# ADC.net
KiCad netlist of a schematic drawn in Altium Designer
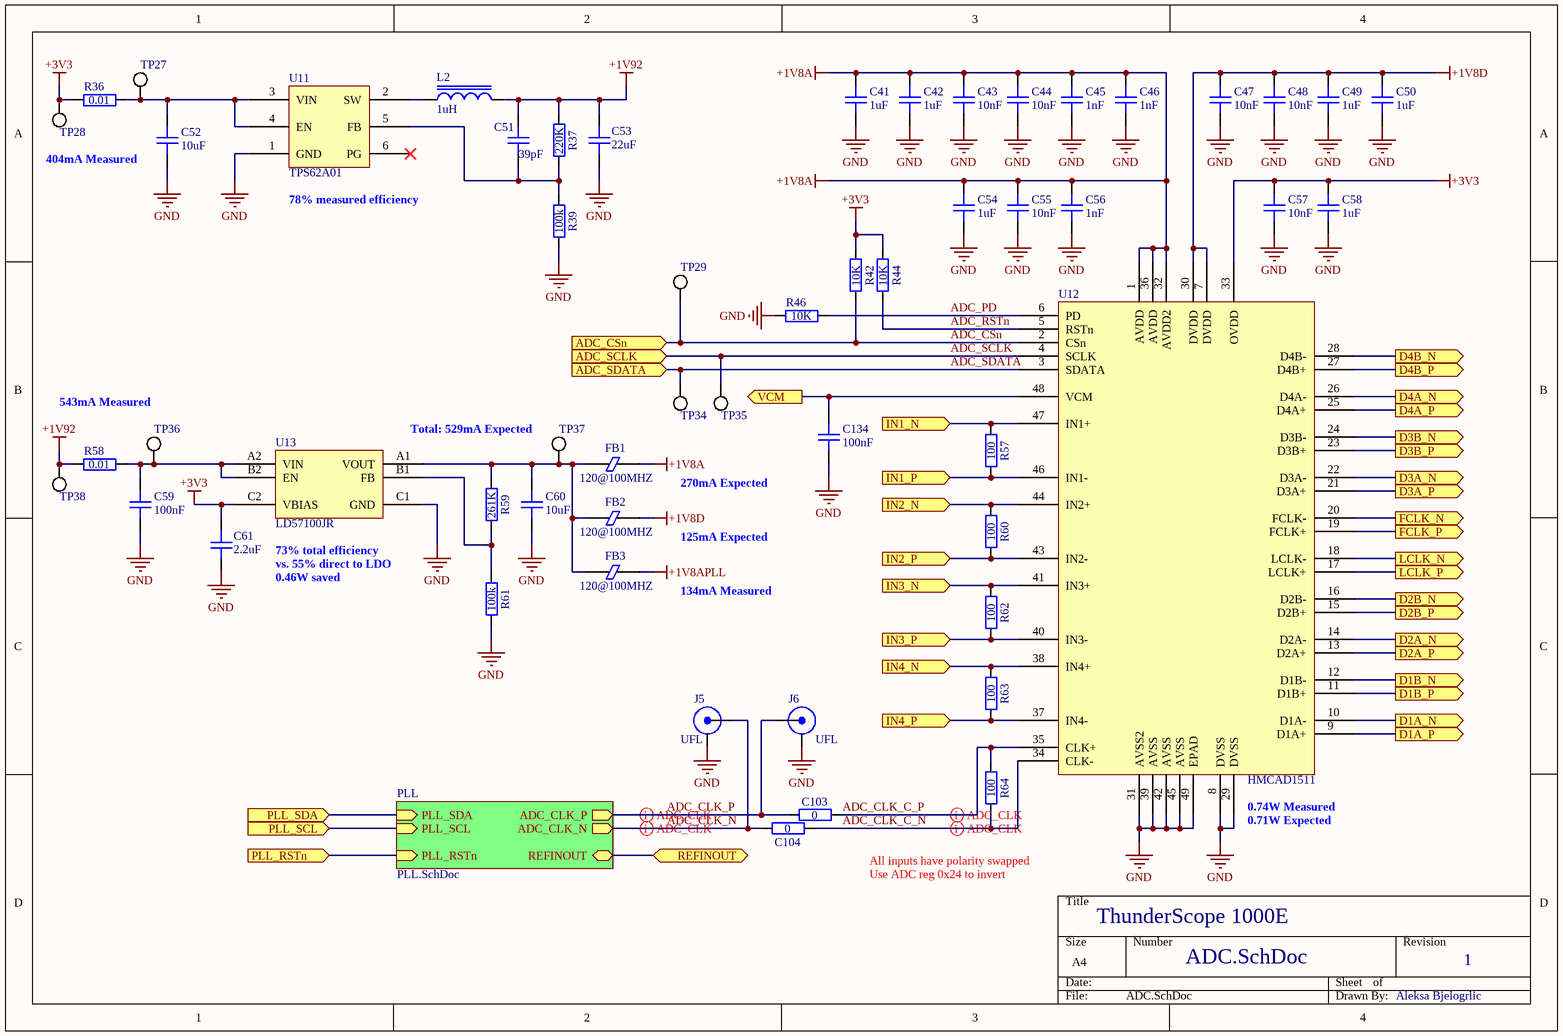
[diagram p0: ADC.SchDoc]

(export (version "E")
  (design (tool "Eeschema 10.0.6"))
  (components
    (comp (ref "C41")
      (value "1uF")
      (footprint "GEN_C_0402")
      (libsource (lib "DSO") (part "CAP 1uF 25V X5R 0402"))
    )
    (comp (ref "C42")
      (value "1uF")
      (footprint "GEN_C_0402")
      (libsource (lib "DSO") (part "CAP 1uF 25V X5R 0402"))
    )
    (comp (ref "C43")
      (value "10nF")
      (footprint "GEN_C_0402")
      (libsource (lib "DSO") (part "CAP 10nF 50V X7R 0402"))
    )
    (comp (ref "C44")
      (value "10nF")
      (footprint "GEN_C_0402")
      (libsource (lib "DSO") (part "CAP 10nF 50V X7R 0402"))
    )
    (comp (ref "C45")
      (value "1nF")
      (footprint "GEN_C_0402")
      (libsource (lib "DSO") (part "CAP 1nF 50V C0G 0402"))
    )
    (comp (ref "C46")
      (value "1nF")
      (footprint "GEN_C_0402")
      (libsource (lib "DSO") (part "CAP 1nF 50V C0G 0402"))
    )
    (comp (ref "C47")
      (value "10nF")
      (footprint "GEN_C_0402")
      (libsource (lib "DSO") (part "CAP 10nF 50V X7R 0402"))
    )
    (comp (ref "C48")
      (value "10nF")
      (footprint "GEN_C_0402")
      (libsource (lib "DSO") (part "CAP 10nF 50V X7R 0402"))
    )
    (comp (ref "C49")
      (value "1uF")
      (footprint "GEN_C_0402")
      (libsource (lib "DSO") (part "CAP 1uF 25V X5R 0402"))
    )
    (comp (ref "C50")
      (value "1uF")
      (footprint "GEN_C_0402")
      (libsource (lib "DSO") (part "CAP 1uF 25V X5R 0402"))
    )
    (comp (ref "C51")
      (value "39pF")
      (footprint "GEN_C_0402")
      (libsource (lib "DSO") (part "CAP 39pF 50V C0G 0402"))
    )
    (comp (ref "C52")
      (value "10uF")
      (footprint "GEN_C_0603")
      (libsource (lib "DSO") (part "CAP 10uF 10V X5R 0603"))
    )
    (comp (ref "C53")
      (value "22uF")
      (footprint "GEN_C_0805")
      (libsource (lib "DSO") (part "CAP 22uF 25V X5R 0805"))
    )
    (comp (ref "C54")
      (value "1uF")
      (footprint "GEN_C_0402")
      (libsource (lib "DSO") (part "CAP 1uF 25V X5R 0402"))
    )
    (comp (ref "C55")
      (value "10nF")
      (footprint "GEN_C_0402")
      (libsource (lib "DSO") (part "CAP 10nF 50V X7R 0402"))
    )
    (comp (ref "C56")
      (value "1nF")
      (footprint "GEN_C_0402")
      (libsource (lib "DSO") (part "CAP 1nF 50V C0G 0402"))
    )
    (comp (ref "C57")
      (value "10nF")
      (footprint "GEN_C_0402")
      (libsource (lib "DSO") (part "CAP 10nF 50V X7R 0402"))
    )
    (comp (ref "C58")
      (value "1uF")
      (footprint "GEN_C_0402")
      (libsource (lib "DSO") (part "CAP 1uF 25V X5R 0402"))
    )
    (comp (ref "C59")
      (value "100nF")
      (footprint "GEN_C_0402")
      (libsource (lib "DSO") (part "CAP 100nF 16V X7R 0402"))
    )
    (comp (ref "C60")
      (value "10uF")
      (footprint "GEN_C_0603")
      (libsource (lib "DSO") (part "CAP 10uF 10V X5R 0603"))
    )
    (comp (ref "C61")
      (value "2.2uF")
      (footprint "GEN_C_0402")
      (libsource (lib "DSO") (part "CAP 2.2uF 10V X5R 0402"))
    )
    (comp (ref "C103")
      (value "0")
      (footprint "GEN_R_0402")
      (fields
        (field (name "MANUFACTURER") "Yageo")
        (field (name "MANUFACTURER PART NUMBER") "RC0402JR-070RL")
      )
      (libsource (lib "DSO") (part "RES 0 OHM 1/16W 0402"))
    )
    (comp (ref "C104")
      (value "0")
      (footprint "GEN_R_0402")
      (fields
        (field (name "MANUFACTURER") "Yageo")
        (field (name "MANUFACTURER PART NUMBER") "RC0402JR-070RL")
      )
      (libsource (lib "DSO") (part "RES 0 OHM 1/16W 0402"))
    )
    (comp (ref "C134")
      (value "100nF")
      (footprint "GEN_C_0402")
      (libsource (lib "DSO") (part "CAP 100nF 16V X7R 0402"))
    )
    (comp (ref "FB1")
      (value "120@100MHZ")
      (footprint "GEN_R_0402")
      (libsource (lib "DSO") (part "FERRITE BEAD 120 OHM 0402"))
    )
    (comp (ref "FB2")
      (value "120@100MHZ")
      (footprint "GEN_R_0402")
      (libsource (lib "DSO") (part "FERRITE BEAD 120 OHM 0402"))
    )
    (comp (ref "FB3")
      (value "120@100MHZ")
      (footprint "GEN_R_0402")
      (libsource (lib "DSO") (part "FERRITE BEAD 120 OHM 0402"))
    )
    (comp (ref "J5") (value "UFL") (footprint "TE_2334884-1") (libsource (lib "DSO") (part "UFL Jack SMD")))
    (comp (ref "J6") (value "UFL") (footprint "TE_2334884-1") (libsource (lib "DSO") (part "UFL Jack SMD")))
    (comp (ref "L2")
      (value "1uH")
      (footprint "GEN_L_1210")
      (libsource (lib "DSO") (part "IND 1uH 3.1A 45 MOHM 1210"))
    )
    (comp (ref "R36")
      (value "0.01")
      (footprint "GEN_R_0603")
      (fields (field (name "TOLERANCE") "1%"))
      (libsource (lib "DSO") (part "RES 0.01 OHM 1% 1/4W 0603"))
    )
    (comp (ref "R37")
      (value "220K")
      (footprint "GEN_R_0402")
      (fields (field (name "TOLERANCE") "1%"))
      (libsource (lib "DSO") (part "RES 220K OHM 1% 1/16W 0402"))
    )
    (comp (ref "R39")
      (value "100k")
      (footprint "GEN_R_0402")
      (fields (field (name "TOLERANCE") "1%"))
      (libsource (lib "DSO") (part "RES 100K OHM 1% 1/10W 0402"))
    )
    (comp (ref "R42")
      (value "10K")
      (footprint "GEN_R_0402")
      (fields (field (name "TOLERANCE") "1%"))
      (libsource (lib "DSO") (part "RES 10K OHM 1% 1/10W 0402"))
    )
    (comp (ref "R44")
      (value "10K")
      (footprint "GEN_R_0402")
      (fields (field (name "TOLERANCE") "1%"))
      (libsource (lib "DSO") (part "RES 10K OHM 1% 1/10W 0402"))
    )
    (comp (ref "R46")
      (value "10K")
      (footprint "GEN_R_0402")
      (fields (field (name "TOLERANCE") "1%"))
      (libsource (lib "") (part "RES 10K OHM 1% 1/10W 0402_1"))
    )
    (comp (ref "R57")
      (value "100")
      (footprint "GEN_R_0402")
      (fields (field (name "TOLERANCE") "1%"))
      (libsource (lib "DSO") (part "RES 100 OHM 1% 1/10W 0402"))
    )
    (comp (ref "R58")
      (value "0.01")
      (footprint "GEN_R_0603")
      (fields (field (name "TOLERANCE") "1%"))
      (libsource (lib "DSO") (part "RES 0.01 OHM 1% 1/4W 0603"))
    )
    (comp (ref "R59")
      (value "261K")
      (footprint "GEN_R_0402")
      (fields (field (name "TOLERANCE") "1%"))
      (libsource (lib "DSO") (part "RES 261K OHM 1% 1/16W 0402"))
    )
    (comp (ref "R60")
      (value "100")
      (footprint "GEN_R_0402")
      (fields (field (name "TOLERANCE") "1%"))
      (libsource (lib "DSO") (part "RES 100 OHM 1% 1/10W 0402"))
    )
    (comp (ref "R61")
      (value "100k")
      (footprint "GEN_R_0402")
      (fields (field (name "TOLERANCE") "1%"))
      (libsource (lib "DSO") (part "RES 100K OHM 1% 1/10W 0402"))
    )
    (comp (ref "R62")
      (value "100")
      (footprint "GEN_R_0402")
      (fields (field (name "TOLERANCE") "1%"))
      (libsource (lib "DSO") (part "RES 100 OHM 1% 1/10W 0402"))
    )
    (comp (ref "R63")
      (value "100")
      (footprint "GEN_R_0402")
      (fields (field (name "TOLERANCE") "1%"))
      (libsource (lib "DSO") (part "RES 100 OHM 1% 1/10W 0402"))
    )
    (comp (ref "R64")
      (value "100")
      (footprint "GEN_R_0402")
      (fields (field (name "TOLERANCE") "1%"))
      (libsource (lib "DSO") (part "RES 100 OHM 1% 1/10W 0402"))
    )
    (comp (ref "TP27") (value "PCB") (footprint "GEN_TP_PCB") (libsource (lib "DSO") (part "TP PCB 1mm")))
    (comp (ref "TP28") (value "PCB") (footprint "GEN_TP_PCB") (libsource (lib "DSO") (part "TP PCB 1mm")))
    (comp (ref "TP29") (value "PCB") (footprint "GEN_TP_PCB") (libsource (lib "DSO") (part "TP PCB 1mm")))
    (comp (ref "TP34") (value "PCB") (footprint "GEN_TP_PCB") (libsource (lib "DSO") (part "TP PCB 1mm")))
    (comp (ref "TP35") (value "PCB") (footprint "GEN_TP_PCB") (libsource (lib "DSO") (part "TP PCB 1mm")))
    (comp (ref "TP36") (value "PCB") (footprint "GEN_TP_PCB") (libsource (lib "DSO") (part "TP PCB 1mm")))
    (comp (ref "TP37") (value "PCB") (footprint "GEN_TP_PCB") (libsource (lib "DSO") (part "TP PCB 1mm")))
    (comp (ref "TP38") (value "PCB") (footprint "GEN_TP_PCB") (libsource (lib "DSO") (part "TP PCB 1mm")))
    (comp (ref "U11")
      (value "TPS62A01")
      (footprint "TI_SOT563_DRL0006A")
      (libsource (lib "DSO") (part "IC BUCK TPS62A01"))
    )
    (comp (ref "U12")
      (value "HMCAD1511")
      (footprint "AD_QFN48_LP7")
      (libsource (lib "DSO") (part "IC ADC HMCAD1511"))
    )
    (comp (ref "U13")
      (value "LD57100JR")
      (footprint "ST_FlipChip6")
      (libsource (lib "DSO") (part "IC LDO LD57100JR"))
    )
  )
  (nets
    (net (code "1") (name "+1V8A") (class "Default")
      (node (ref "C41") (pin "2") (pinfunction "2_2") (pintype "passive"))
      (node (ref "C42") (pin "2") (pinfunction "2_2") (pintype "passive"))
      (node (ref "C43") (pin "2") (pinfunction "2_2") (pintype "passive"))
      (node (ref "C44") (pin "2") (pinfunction "2_2") (pintype "passive"))
      (node (ref "C45") (pin "2") (pinfunction "2_2") (pintype "passive"))
      (node (ref "C46") (pin "2") (pinfunction "2_2") (pintype "passive"))
      (node (ref "C54") (pin "2") (pinfunction "2_2") (pintype "passive"))
      (node (ref "C55") (pin "2") (pinfunction "2_2") (pintype "passive"))
      (node (ref "C56") (pin "2") (pinfunction "2_2") (pintype "passive"))
      (node (ref "FB1") (pin "2") (pinfunction "2_2") (pintype "passive"))
      (node (ref "U12") (pin "1") (pinfunction "AVDD_1") (pintype "passive"))
      (node (ref "U12") (pin "32") (pinfunction "AVDD2_32") (pintype "passive"))
      (node (ref "U12") (pin "36") (pinfunction "AVDD_36") (pintype "passive"))
    )
    (net (code "2") (name "+1V8APLL") (class "Default")
      (node (ref "FB3") (pin "2") (pinfunction "2_2") (pintype "passive"))
    )
    (net (code "3") (name "+1V8D") (class "Default")
      (node (ref "C47") (pin "2") (pinfunction "2_2") (pintype "passive"))
      (node (ref "C48") (pin "2") (pinfunction "2_2") (pintype "passive"))
      (node (ref "C49") (pin "2") (pinfunction "2_2") (pintype "passive"))
      (node (ref "C50") (pin "2") (pinfunction "2_2") (pintype "passive"))
      (node (ref "FB2") (pin "2") (pinfunction "2_2") (pintype "passive"))
      (node (ref "U12") (pin "30") (pinfunction "DVDD_30") (pintype "passive"))
      (node (ref "U12") (pin "7") (pinfunction "DVDD_7") (pintype "passive"))
    )
    (net (code "4") (name "+1V92") (class "Default")
      (node (ref "C51") (pin "2") (pinfunction "2_2") (pintype "passive"))
      (node (ref "C53") (pin "2") (pinfunction "2_2") (pintype "passive"))
      (node (ref "L2") (pin "2") (pinfunction "2_2") (pintype "passive"))
      (node (ref "R37") (pin "2") (pinfunction "2_2") (pintype "passive"))
      (node (ref "R58") (pin "1") (pinfunction "1_1") (pintype "passive"))
      (node (ref "TP38") (pin "1") (pinfunction "1_1") (pintype "passive"))
    )
    (net (code "5") (name "+3V3") (class "Default")
      (node (ref "C57") (pin "2") (pinfunction "2_2") (pintype "passive"))
      (node (ref "C58") (pin "2") (pinfunction "2_2") (pintype "passive"))
      (node (ref "C61") (pin "2") (pinfunction "2_2") (pintype "passive"))
      (node (ref "R36") (pin "1") (pinfunction "1_1") (pintype "passive"))
      (node (ref "R42") (pin "2") (pinfunction "2_2") (pintype "passive"))
      (node (ref "R44") (pin "2") (pinfunction "2_2") (pintype "passive"))
      (node (ref "TP28") (pin "1") (pinfunction "1_1") (pintype "passive"))
      (node (ref "U12") (pin "33") (pinfunction "OVDD_33") (pintype "passive"))
      (node (ref "U13") (pin "C2") (pinfunction "VBIAS_C2") (pintype "passive"))
    )
    (net (code "6") (name "/ADC_CLK_C_N") (class "Default")
      (node (ref "C104") (pin "1") (pinfunction "1_1") (pintype "passive"))
      (node (ref "R64") (pin "1") (pinfunction "1_1") (pintype "passive"))
      (node (ref "U12") (pin "34") (pinfunction "CLK-_34") (pintype "passive"))
    )
    (net (code "7") (name "/ADC_CLK_C_P") (class "Default")
      (node (ref "C103") (pin "1") (pinfunction "1_1") (pintype "passive"))
      (node (ref "R64") (pin "2") (pinfunction "2_2") (pintype "passive"))
      (node (ref "U12") (pin "35") (pinfunction "CLK+_35") (pintype "passive"))
    )
    (net (code "8") (name "/ADC_CLK_N") (class "Default")
      (node (ref "C104") (pin "2") (pinfunction "2_2") (pintype "passive"))
      (node (ref "J5") (pin "1") (pinfunction "Signal_1") (pintype "passive"))
    )
    (net (code "9") (name "/ADC_CLK_P") (class "Default")
      (node (ref "C103") (pin "2") (pinfunction "2_2") (pintype "passive"))
      (node (ref "J6") (pin "1") (pinfunction "Signal_1") (pintype "passive"))
    )
    (net (code "10") (name "/ADC_CSn") (class "Default")
      (node (ref "R42") (pin "1") (pinfunction "1_1") (pintype "passive"))
      (node (ref "TP29") (pin "1") (pinfunction "1_1") (pintype "passive"))
      (node (ref "U12") (pin "2") (pinfunction "CSn_2") (pintype "passive"))
    )
    (net (code "11") (name "/ADC_PD") (class "Default")
      (node (ref "R46") (pin "1") (pinfunction "1_1") (pintype "passive"))
      (node (ref "U12") (pin "6") (pinfunction "PD_6") (pintype "passive"))
    )
    (net (code "12") (name "/ADC_RSTn") (class "Default")
      (node (ref "R44") (pin "1") (pinfunction "1_1") (pintype "passive"))
      (node (ref "U12") (pin "5") (pinfunction "RSTn_5") (pintype "passive"))
    )
    (net (code "13") (name "/ADC_SCLK") (class "Default")
      (node (ref "TP35") (pin "1") (pinfunction "1_1") (pintype "passive"))
      (node (ref "U12") (pin "4") (pinfunction "SCLK_4") (pintype "passive"))
    )
    (net (code "14") (name "/ADC_SDATA") (class "Default")
      (node (ref "TP34") (pin "1") (pinfunction "1_1") (pintype "passive"))
      (node (ref "U12") (pin "3") (pinfunction "SDATA_3") (pintype "passive"))
    )
    (net (code "15") (name "/D1A_N") (class "Default")
      (node (ref "U12") (pin "10") (pinfunction "D1A-_10") (pintype "passive"))
    )
    (net (code "16") (name "/D1A_P") (class "Default")
      (node (ref "U12") (pin "9") (pinfunction "D1A+_9") (pintype "passive"))
    )
    (net (code "17") (name "/D1B_N") (class "Default")
      (node (ref "U12") (pin "12") (pinfunction "D1B-_12") (pintype "passive"))
    )
    (net (code "18") (name "/D1B_P") (class "Default")
      (node (ref "U12") (pin "11") (pinfunction "D1B+_11") (pintype "passive"))
    )
    (net (code "19") (name "/D2A_N") (class "Default")
      (node (ref "U12") (pin "14") (pinfunction "D2A-_14") (pintype "passive"))
    )
    (net (code "20") (name "/D2A_P") (class "Default")
      (node (ref "U12") (pin "13") (pinfunction "D2A+_13") (pintype "passive"))
    )
    (net (code "21") (name "/D2B_N") (class "Default")
      (node (ref "U12") (pin "16") (pinfunction "D2B-_16") (pintype "passive"))
    )
    (net (code "22") (name "/D2B_P") (class "Default")
      (node (ref "U12") (pin "15") (pinfunction "D2B+_15") (pintype "passive"))
    )
    (net (code "23") (name "/D3A_N") (class "Default")
      (node (ref "U12") (pin "22") (pinfunction "D3A-_22") (pintype "passive"))
    )
    (net (code "24") (name "/D3A_P") (class "Default")
      (node (ref "U12") (pin "21") (pinfunction "D3A+_21") (pintype "passive"))
    )
    (net (code "25") (name "/D3B_N") (class "Default")
      (node (ref "U12") (pin "24") (pinfunction "D3B-_24") (pintype "passive"))
    )
    (net (code "26") (name "/D3B_P") (class "Default")
      (node (ref "U12") (pin "23") (pinfunction "D3B+_23") (pintype "passive"))
    )
    (net (code "27") (name "/D4A_N") (class "Default")
      (node (ref "U12") (pin "26") (pinfunction "D4A-_26") (pintype "passive"))
    )
    (net (code "28") (name "/D4A_P") (class "Default")
      (node (ref "U12") (pin "25") (pinfunction "D4A+_25") (pintype "passive"))
    )
    (net (code "29") (name "/D4B_N") (class "Default")
      (node (ref "U12") (pin "28") (pinfunction "D4B-_28") (pintype "passive"))
    )
    (net (code "30") (name "/D4B_P") (class "Default")
      (node (ref "U12") (pin "27") (pinfunction "D4B+_27") (pintype "passive"))
    )
    (net (code "31") (name "/FCLK_N") (class "Default")
      (node (ref "U12") (pin "20") (pinfunction "FCLK-_20") (pintype "passive"))
    )
    (net (code "32") (name "/FCLK_P") (class "Default")
      (node (ref "U12") (pin "19") (pinfunction "FCLK+_19") (pintype "passive"))
    )
    (net (code "33") (name "/IN1_N") (class "Default")
      (node (ref "R57") (pin "2") (pinfunction "2_2") (pintype "passive"))
      (node (ref "U12") (pin "47") (pinfunction "IN1+_47") (pintype "passive"))
    )
    (net (code "34") (name "/IN1_P") (class "Default")
      (node (ref "R57") (pin "1") (pinfunction "1_1") (pintype "passive"))
      (node (ref "U12") (pin "46") (pinfunction "IN1-_46") (pintype "passive"))
    )
    (net (code "35") (name "/IN2_N") (class "Default")
      (node (ref "R60") (pin "2") (pinfunction "2_2") (pintype "passive"))
      (node (ref "U12") (pin "44") (pinfunction "IN2+_44") (pintype "passive"))
    )
    (net (code "36") (name "/IN2_P") (class "Default")
      (node (ref "R60") (pin "1") (pinfunction "1_1") (pintype "passive"))
      (node (ref "U12") (pin "43") (pinfunction "IN2-_43") (pintype "passive"))
    )
    (net (code "37") (name "/IN3_N") (class "Default")
      (node (ref "R62") (pin "2") (pinfunction "2_2") (pintype "passive"))
      (node (ref "U12") (pin "41") (pinfunction "IN3+_41") (pintype "passive"))
    )
    (net (code "38") (name "/IN3_P") (class "Default")
      (node (ref "R62") (pin "1") (pinfunction "1_1") (pintype "passive"))
      (node (ref "U12") (pin "40") (pinfunction "IN3-_40") (pintype "passive"))
    )
    (net (code "39") (name "/IN4_N") (class "Default")
      (node (ref "R63") (pin "2") (pinfunction "2_2") (pintype "passive"))
      (node (ref "U12") (pin "38") (pinfunction "IN4+_38") (pintype "passive"))
    )
    (net (code "40") (name "/IN4_P") (class "Default")
      (node (ref "R63") (pin "1") (pinfunction "1_1") (pintype "passive"))
      (node (ref "U12") (pin "37") (pinfunction "IN4-_37") (pintype "passive"))
    )
    (net (code "41") (name "/LCLK_N") (class "Default")
      (node (ref "U12") (pin "18") (pinfunction "LCLK-_18") (pintype "passive"))
    )
    (net (code "42") (name "/LCLK_P") (class "Default")
      (node (ref "U12") (pin "17") (pinfunction "LCLK+_17") (pintype "passive"))
    )
    (net (code "47") (name "/VCM") (class "Default")
      (node (ref "C134") (pin "2") (pinfunction "2_2") (pintype "passive"))
      (node (ref "U12") (pin "48") (pinfunction "VCM_48") (pintype "passive"))
    )
    (net (code "48") (name "GND") (class "Default")
      (node (ref "C134") (pin "1") (pinfunction "1_1") (pintype "passive"))
      (node (ref "C41") (pin "1") (pinfunction "1_1") (pintype "passive"))
      (node (ref "C42") (pin "1") (pinfunction "1_1") (pintype "passive"))
      (node (ref "C43") (pin "1") (pinfunction "1_1") (pintype "passive"))
      (node (ref "C44") (pin "1") (pinfunction "1_1") (pintype "passive"))
      (node (ref "C45") (pin "1") (pinfunction "1_1") (pintype "passive"))
      (node (ref "C46") (pin "1") (pinfunction "1_1") (pintype "passive"))
      (node (ref "C47") (pin "1") (pinfunction "1_1") (pintype "passive"))
      (node (ref "C48") (pin "1") (pinfunction "1_1") (pintype "passive"))
      (node (ref "C49") (pin "1") (pinfunction "1_1") (pintype "passive"))
      (node (ref "C50") (pin "1") (pinfunction "1_1") (pintype "passive"))
      (node (ref "C52") (pin "1") (pinfunction "1_1") (pintype "passive"))
      (node (ref "C53") (pin "1") (pinfunction "1_1") (pintype "passive"))
      (node (ref "C54") (pin "1") (pinfunction "1_1") (pintype "passive"))
      (node (ref "C55") (pin "1") (pinfunction "1_1") (pintype "passive"))
      (node (ref "C56") (pin "1") (pinfunction "1_1") (pintype "passive"))
      (node (ref "C57") (pin "1") (pinfunction "1_1") (pintype "passive"))
      (node (ref "C58") (pin "1") (pinfunction "1_1") (pintype "passive"))
      (node (ref "C59") (pin "1") (pinfunction "1_1") (pintype "passive"))
      (node (ref "C60") (pin "1") (pinfunction "1_1") (pintype "passive"))
      (node (ref "C61") (pin "1") (pinfunction "1_1") (pintype "passive"))
      (node (ref "J5") (pin "2") (pinfunction "SHIELD_2") (pintype "passive"))
      (node (ref "J6") (pin "2") (pinfunction "SHIELD_2") (pintype "passive"))
      (node (ref "R39") (pin "1") (pinfunction "1_1") (pintype "passive"))
      (node (ref "R46") (pin "2") (pinfunction "2_2") (pintype "passive"))
      (node (ref "R61") (pin "1") (pinfunction "1_1") (pintype "passive"))
      (node (ref "U11") (pin "1") (pinfunction "GND_1") (pintype "power_in"))
      (node (ref "U12") (pin "29") (pinfunction "DVSS_29") (pintype "passive"))
      (node (ref "U12") (pin "31") (pinfunction "AVSS2_31") (pintype "passive"))
      (node (ref "U12") (pin "39") (pinfunction "AVSS_39") (pintype "passive"))
      (node (ref "U12") (pin "42") (pinfunction "AVSS_42") (pintype "passive"))
      (node (ref "U12") (pin "45") (pinfunction "AVSS_45") (pintype "passive"))
      (node (ref "U12") (pin "49") (pinfunction "EPAD_49") (pintype "passive"))
      (node (ref "U12") (pin "8") (pinfunction "DVSS_8") (pintype "passive"))
      (node (ref "U13") (pin "C1") (pinfunction "GND_C1") (pintype "passive"))
    )
    (net (code "49") (name "Net-(U11-EN)") (class "Default")
      (node (ref "C52") (pin "2") (pinfunction "2_2") (pintype "passive"))
      (node (ref "R36") (pin "2") (pinfunction "2_2") (pintype "passive"))
      (node (ref "TP27") (pin "1") (pinfunction "1_1") (pintype "passive"))
      (node (ref "U11") (pin "3") (pinfunction "VIN_3") (pintype "power_in"))
      (node (ref "U11") (pin "4") (pinfunction "EN_4") (pintype "passive"))
    )
    (net (code "50") (name "Net-(U11-FB)") (class "Default")
      (node (ref "C51") (pin "1") (pinfunction "1_1") (pintype "passive"))
      (node (ref "R37") (pin "1") (pinfunction "1_1") (pintype "passive"))
      (node (ref "R39") (pin "2") (pinfunction "2_2") (pintype "passive"))
      (node (ref "U11") (pin "5") (pinfunction "FB_5") (pintype "passive"))
    )
    (net (code "51") (name "Net-(U11-SW)") (class "Default")
      (node (ref "L2") (pin "1") (pinfunction "1_1") (pintype "passive"))
      (node (ref "U11") (pin "2") (pinfunction "SW_2") (pintype "passive"))
    )
    (net (code "52") (name "Net-(U13-EN)") (class "Default")
      (node (ref "C59") (pin "2") (pinfunction "2_2") (pintype "passive"))
      (node (ref "R58") (pin "2") (pinfunction "2_2") (pintype "passive"))
      (node (ref "TP36") (pin "1") (pinfunction "1_1") (pintype "passive"))
      (node (ref "U13") (pin "A2") (pinfunction "VIN_A2") (pintype "passive"))
      (node (ref "U13") (pin "B2") (pinfunction "EN_B2") (pintype "passive"))
    )
    (net (code "53") (name "Net-(U13-FB)") (class "Default")
      (node (ref "R59") (pin "1") (pinfunction "1_1") (pintype "passive"))
      (node (ref "R61") (pin "2") (pinfunction "2_2") (pintype "passive"))
      (node (ref "U13") (pin "B1") (pinfunction "FB_B1") (pintype "passive"))
    )
    (net (code "54") (name "Net-(U13-VOUT)") (class "Default")
      (node (ref "C60") (pin "2") (pinfunction "2_2") (pintype "passive"))
      (node (ref "FB1") (pin "1") (pinfunction "1_1") (pintype "passive"))
      (node (ref "FB2") (pin "1") (pinfunction "1_1") (pintype "passive"))
      (node (ref "FB3") (pin "1") (pinfunction "1_1") (pintype "passive"))
      (node (ref "R59") (pin "2") (pinfunction "2_2") (pintype "passive"))
      (node (ref "TP37") (pin "1") (pinfunction "1_1") (pintype "passive"))
      (node (ref "U13") (pin "A1") (pinfunction "VOUT_A1") (pintype "passive"))
    )
    (net (code "55") (name "unconnected-(U11-PG-Pad6)") (class "Default")
      (node (ref "U11") (pin "6") (pinfunction "PG_6") (pintype "passive+no_connect"))
    )
  )
)
